# design.net
KiCad netlist of a schematic drawn in Altium Designer
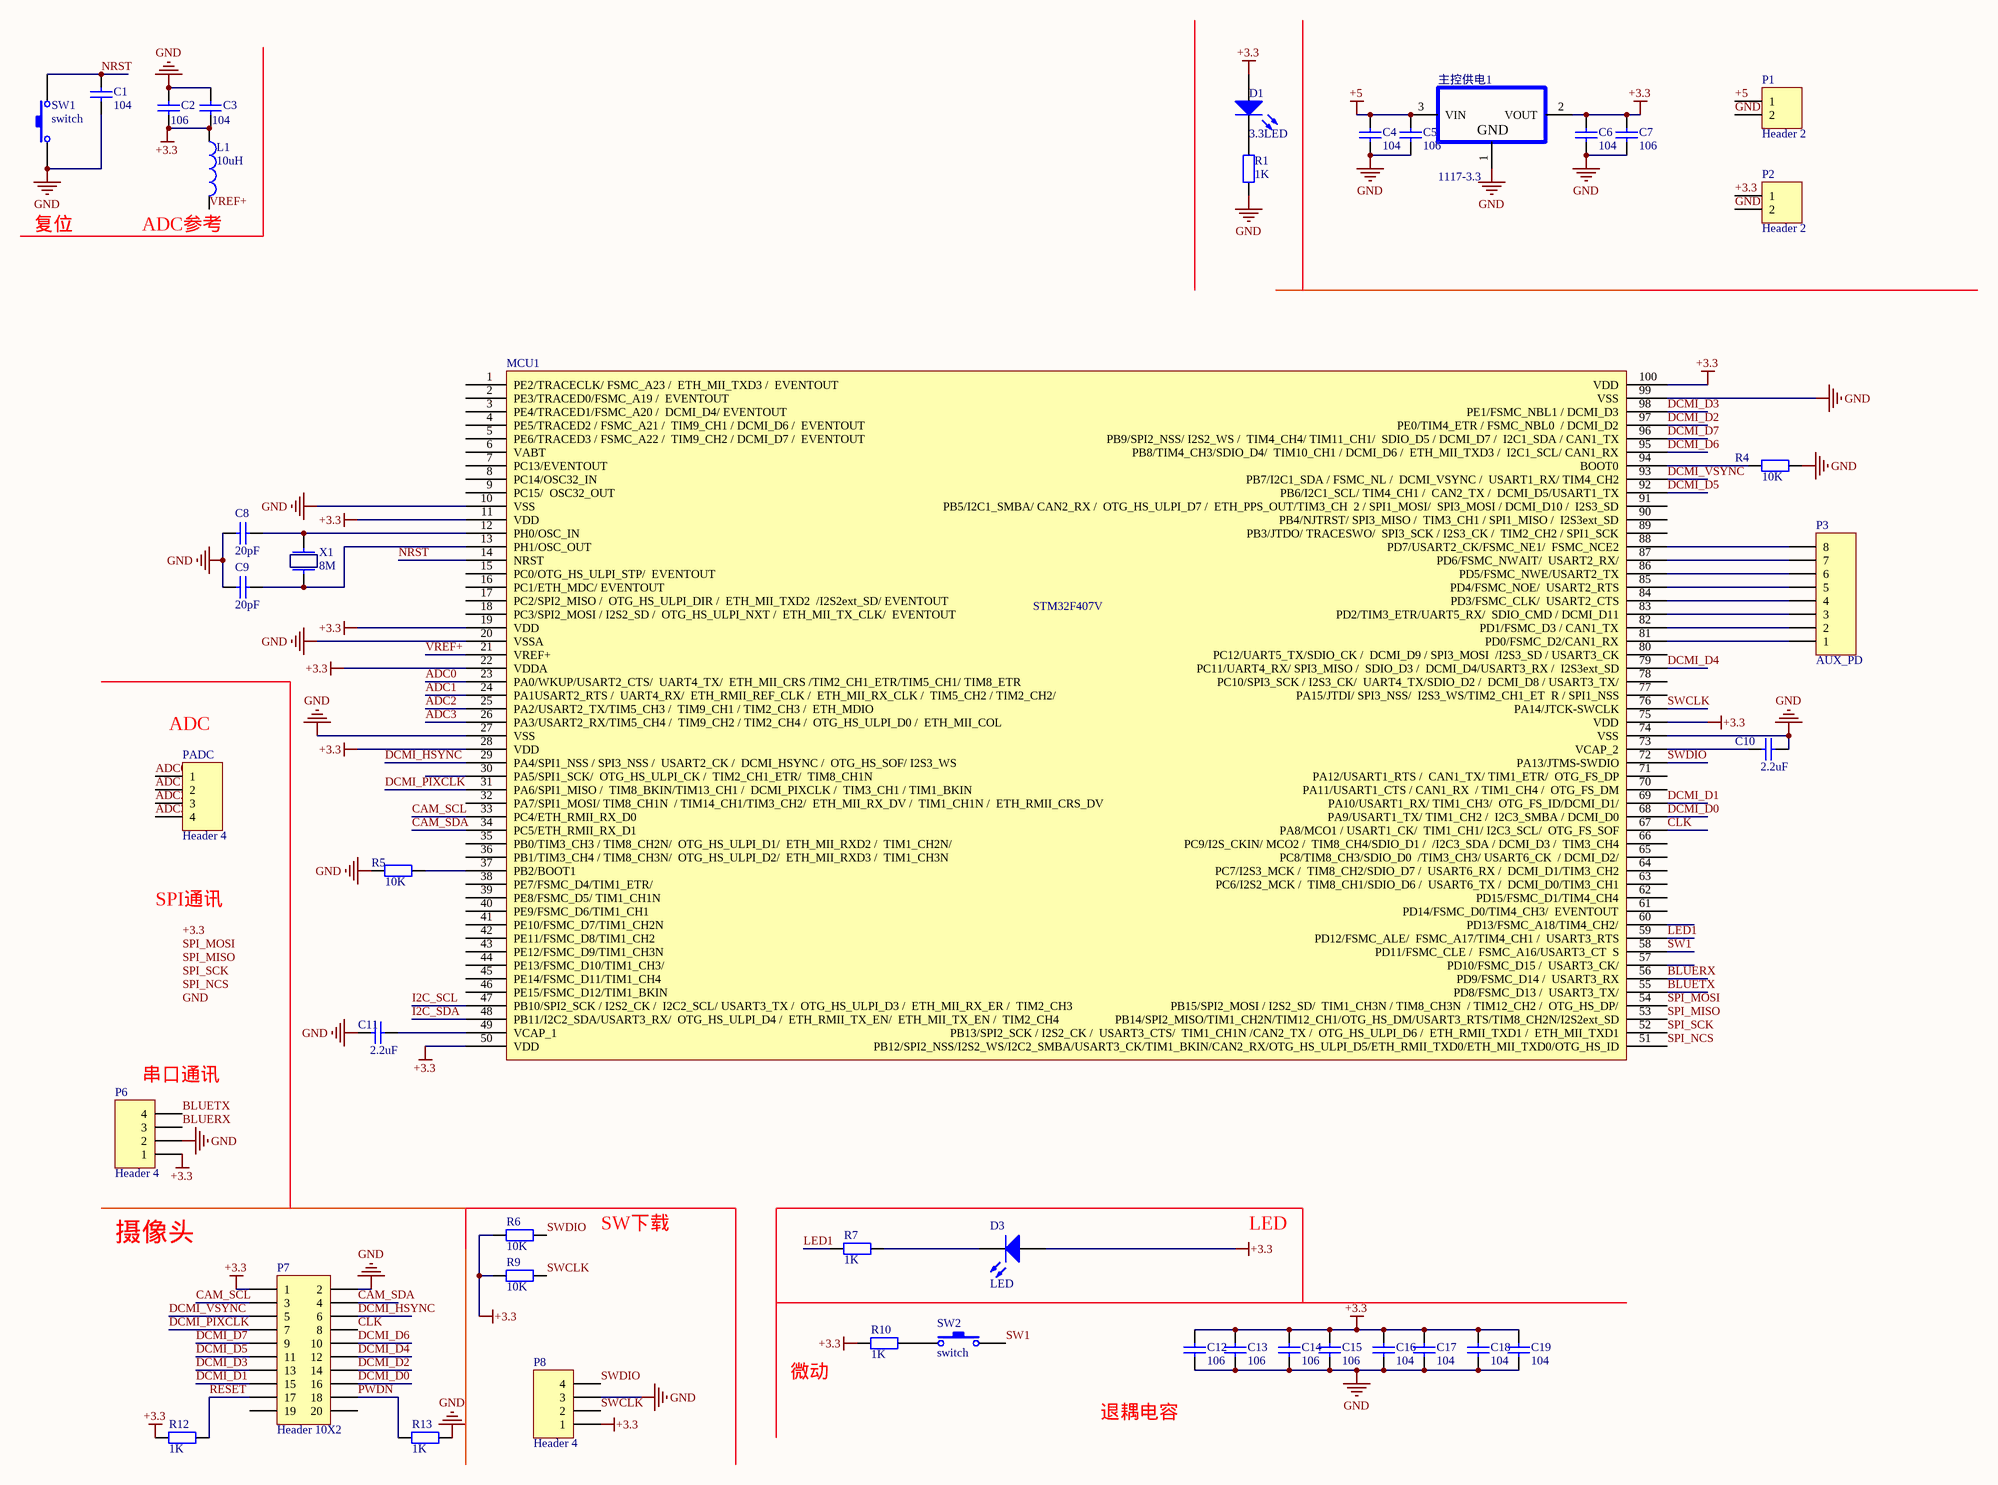
[diagram p0: 摄像头小王子.SchDoc]

(export (version "E")
  (design (tool "Eeschema 10.0.6"))
  (components
    (comp (ref "C1")
      (value "104")
      (footprint "6-0805_N")
      (libsource (lib "lucifer-PCBLIB_V2.0（这是老蒋的）") (part "cap"))
    )
    (comp (ref "C2")
      (value "106")
      (footprint "6-0805_N")
      (description "Capacitor")
      (fields (field (name "Comment") "Cap") (field (name "PUBLISHER") "Altium Limited"))
      (libsource (lib "Miscellaneous Devices") (part "Cap"))
    )
    (comp (ref "C3")
      (value "104")
      (footprint "6-0805_N")
      (description "Capacitor")
      (fields (field (name "Comment") "Cap") (field (name "PUBLISHER") "Altium Limited"))
      (libsource (lib "Miscellaneous Devices") (part "Cap"))
    )
    (comp (ref "C4")
      (value "104")
      (footprint "6-0805_N")
      (libsource (lib "lucifer-PCBLIB_V2.0（这是老蒋的）") (part "cap"))
    )
    (comp (ref "C5")
      (value "106")
      (footprint "6-0805_N")
      (libsource (lib "lucifer-PCBLIB_V2.0（这是老蒋的）") (part "cap"))
    )
    (comp (ref "C6")
      (value "104")
      (footprint "6-0805_N")
      (libsource (lib "lucifer-PCBLIB_V2.0（这是老蒋的）") (part "cap"))
    )
    (comp (ref "C7")
      (value "106")
      (footprint "6-0805_N")
      (libsource (lib "lucifer-PCBLIB_V2.0（这是老蒋的）") (part "cap"))
    )
    (comp (ref "C8")
      (value "20pF")
      (footprint "6-0805_N")
      (libsource (lib "lucifer-PCBLIB_V2.0（这是老蒋的）") (part "cap"))
    )
    (comp (ref "C9")
      (value "20pF")
      (footprint "6-0805_N")
      (libsource (lib "lucifer-PCBLIB_V2.0（这是老蒋的）") (part "cap"))
    )
    (comp (ref "C10")
      (value "2.2uF")
      (footprint "6-0805_N")
      (libsource (lib "lucifer-PCBLIB_V2.0（这是老蒋的）") (part "cap"))
    )
    (comp (ref "C11")
      (value "2.2uF")
      (footprint "6-0805_N")
      (libsource (lib "lucifer-PCBLIB_V2.0（这是老蒋的）") (part "cap"))
    )
    (comp (ref "C12")
      (value "106")
      (footprint "6-0805_N")
      (libsource (lib "lucifer-PCBLIB_V2.0（这是老蒋的）") (part "cap"))
    )
    (comp (ref "C13")
      (value "106")
      (footprint "6-0805_N")
      (libsource (lib "lucifer-PCBLIB_V2.0（这是老蒋的）") (part "cap"))
    )
    (comp (ref "C14")
      (value "106")
      (footprint "6-0805_N")
      (libsource (lib "lucifer-PCBLIB_V2.0（这是老蒋的）") (part "cap"))
    )
    (comp (ref "C15")
      (value "106")
      (footprint "6-0805_N")
      (libsource (lib "lucifer-PCBLIB_V2.0（这是老蒋的）") (part "cap"))
    )
    (comp (ref "C16")
      (value "104")
      (footprint "6-0805_N")
      (libsource (lib "lucifer-PCBLIB_V2.0（这是老蒋的）") (part "cap"))
    )
    (comp (ref "C17")
      (value "104")
      (footprint "6-0805_N")
      (libsource (lib "lucifer-PCBLIB_V2.0（这是老蒋的）") (part "cap"))
    )
    (comp (ref "C18")
      (value "104")
      (footprint "6-0805_N")
      (libsource (lib "lucifer-PCBLIB_V2.0（这是老蒋的）") (part "cap"))
    )
    (comp (ref "C19")
      (value "104")
      (footprint "6-0805_N")
      (libsource (lib "lucifer-PCBLIB_V2.0（这是老蒋的）") (part "cap"))
    )
    (comp (ref "D1")
      (value "3.3LED")
      (footprint "6-0805_N")
      (libsource (lib "lucifer-PCBLIB_V2.0（这是老蒋的）") (part "LED"))
    )
    (comp (ref "D3")
      (value "LED")
      (footprint "6-0805_N")
      (libsource (lib "lucifer-PCBLIB_V2.0（这是老蒋的）") (part "LED"))
    )
    (comp (ref "L1")
      (value "10uH")
      (footprint "6-0805_N")
      (description "Inductor")
      (fields (field (name "PUBLISHER") "Altium Limited"))
      (libsource (lib "Miscellaneous Devices") (part "Inductor"))
    )
    (comp (ref "MCU1") (value "STM32F407V") (footprint "LQFP100") (libsource (lib "我的库") (part "stm32f407")))
    (comp (ref "P1")
      (value "Header 2")
      (footprint "HDR1X2")
      (description "Header, 2-Pin")
      (fields (field (name "PUBLISHER") "Altium Limited"))
      (libsource (lib "Miscellaneous Connectors") (part "Header 2"))
    )
    (comp (ref "P2")
      (value "Header 2")
      (footprint "HDR1X2")
      (description "Header, 2-Pin")
      (fields (field (name "PUBLISHER") "Altium Limited"))
      (libsource (lib "Miscellaneous Connectors") (part "Header 2"))
    )
    (comp (ref "P3")
      (value "AUX_PD")
      (footprint "HDR1X8")
      (description "Header, 8-Pin")
      (fields (field (name "PUBLISHER") "Altium Limited"))
      (libsource (lib "Miscellaneous Connectors") (part "Header 8"))
    )
    (comp (ref "P6")
      (value "Header 4")
      (footprint "HDR1X4")
      (description "Header, 4-Pin")
      (fields (field (name "PUBLISHER") "Altium Limited"))
      (libsource (lib "Miscellaneous Connectors") (part "Header 4"))
    )
    (comp (ref "P7")
      (value "Header 10X2")
      (footprint "HDR2X10")
      (description "Header, 10-Pin, Dual row")
      (fields (field (name "PUBLISHER") "Altium Limited"))
      (libsource (lib "Miscellaneous Connectors") (part "Header 10X2"))
    )
    (comp (ref "P8")
      (value "Header 4")
      (footprint "HDR1X4")
      (description "Header, 4-Pin")
      (fields (field (name "PUBLISHER") "Altium Limited"))
      (libsource (lib "Miscellaneous Connectors") (part "Header 4"))
    )
    (comp (ref "PADC")
      (value "Header 4")
      (footprint "HDR1X4")
      (description "Header, 4-Pin")
      (fields (field (name "PUBLISHER") "Altium Limited"))
      (libsource (lib "") (part "Header 4_1"))
    )
    (comp (ref "R1")
      (value "1K")
      (footprint "6-0805_N")
      (description "small resistor")
      (libsource (lib "") (part "resistor_2"))
    )
    (comp (ref "R4")
      (value "10K")
      (footprint "6-0805_N")
      (description "small resistor")
      (libsource (lib "lucifer-PCBLIB_V2.0（这是老蒋的）") (part "resistor"))
    )
    (comp (ref "R5")
      (value "10K")
      (footprint "6-0805_N")
      (description "small resistor")
      (libsource (lib "") (part "resistor_1"))
    )
    (comp (ref "R6")
      (value "10K")
      (footprint "6-0805_N")
      (description "small resistor")
      (libsource (lib "lucifer-PCBLIB_V2.0（这是老蒋的）") (part "resistor"))
    )
    (comp (ref "R7")
      (value "1K")
      (footprint "6-0805_N")
      (description "small resistor")
      (libsource (lib "lucifer-PCBLIB_V2.0（这是老蒋的）") (part "resistor"))
    )
    (comp (ref "R9")
      (value "10K")
      (footprint "6-0805_N")
      (description "small resistor")
      (libsource (lib "") (part "resistor_1"))
    )
    (comp (ref "R10")
      (value "1K")
      (footprint "6-0805_N")
      (description "small resistor")
      (libsource (lib "lucifer-PCBLIB_V2.0（这是老蒋的）") (part "resistor"))
    )
    (comp (ref "R12")
      (value "1K")
      (footprint "6-0805_N")
      (description "small resistor")
      (libsource (lib "lucifer-PCBLIB_V2.0（这是老蒋的）") (part "resistor"))
    )
    (comp (ref "R13")
      (value "1K")
      (footprint "6-0805_N")
      (description "small resistor")
      (libsource (lib "lucifer-PCBLIB_V2.0（这是老蒋的）") (part "resistor"))
    )
    (comp (ref "SW1")
      (value "switch")
      (footprint "SW_PB2_A1")
      (libsource (lib "lucifer-PCBLIB_V2.0（这是老蒋的）") (part "switch-1"))
    )
    (comp (ref "SW2")
      (value "switch")
      (footprint "SW_PB2_A1")
      (libsource (lib "lucifer-PCBLIB_V2.0（这是老蒋的）") (part "switch-1"))
    )
    (comp (ref "X1")
      (value "8M")
      (footprint "HDR1X3")
      (fields (field (name "Comment") "xtal"))
      (libsource (lib "lucifer-PCBLIB_V2.0（这是老蒋的）") (part "xtal"))
    )
    (comp (ref "主控供电1")
      (value "1117-3.3")
      (footprint "SOT-223")
      (libsource (lib "lucifer-PCBLIB_V2.0（这是老蒋的）") (part "1117M3-3.3"))
    )
  )
  (nets
    (net (code "1") (name "+3.3") (class "Default")
      (node (ref "C12") (pin "2") (pinfunction "2_2") (pintype "passive"))
      (node (ref "C13") (pin "2") (pinfunction "2_2") (pintype "passive"))
      (node (ref "C14") (pin "2") (pinfunction "2_2") (pintype "passive"))
      (node (ref "C15") (pin "2") (pinfunction "2_2") (pintype "passive"))
      (node (ref "C16") (pin "2") (pinfunction "2_2") (pintype "passive"))
      (node (ref "C17") (pin "2") (pinfunction "2_2") (pintype "passive"))
      (node (ref "C18") (pin "2") (pinfunction "2_2") (pintype "passive"))
      (node (ref "C19") (pin "2") (pinfunction "2_2") (pintype "passive"))
      (node (ref "C2") (pin "1") (pinfunction "1_1") (pintype "passive"))
      (node (ref "C3") (pin "1") (pinfunction "1_1") (pintype "passive"))
      (node (ref "C6") (pin "2") (pinfunction "2_2") (pintype "passive"))
      (node (ref "C7") (pin "2") (pinfunction "2_2") (pintype "passive"))
      (node (ref "D1") (pin "1") (pinfunction "A_1") (pintype "passive"))
      (node (ref "D3") (pin "1") (pinfunction "A_1") (pintype "passive"))
      (node (ref "L1") (pin "1") (pinfunction "1_1") (pintype "passive"))
      (node (ref "MCU1") (pin "100") (pinfunction "VDD_100") (pintype "passive"))
      (node (ref "MCU1") (pin "11") (pinfunction "VDD_11") (pintype "passive"))
      (node (ref "MCU1") (pin "19") (pinfunction "VDD_19") (pintype "passive"))
      (node (ref "MCU1") (pin "22") (pinfunction "VDDA_22") (pintype "passive"))
      (node (ref "MCU1") (pin "28") (pinfunction "VDD_28") (pintype "passive"))
      (node (ref "MCU1") (pin "50") (pinfunction "VDD_50") (pintype "passive"))
      (node (ref "MCU1") (pin "75") (pinfunction "VDD_75") (pintype "passive"))
      (node (ref "P2") (pin "1") (pinfunction "1_1") (pintype "passive"))
      (node (ref "P6") (pin "1") (pinfunction "1_1") (pintype "passive"))
      (node (ref "P7") (pin "1") (pinfunction "1_1") (pintype "passive"))
      (node (ref "P8") (pin "1") (pinfunction "1_1") (pintype "passive"))
      (node (ref "R10") (pin "1") (pinfunction "1_1") (pintype "passive"))
      (node (ref "R12") (pin "1") (pinfunction "1_1") (pintype "passive"))
      (node (ref "R6") (pin "1") (pinfunction "1_1") (pintype "passive"))
      (node (ref "R9") (pin "2") (pinfunction "2_2") (pintype "passive"))
      (node (ref "主控供电1") (pin "2") (pinfunction "VOUT_2") (pintype "passive"))
    )
    (net (code "2") (name "+5") (class "Default")
      (node (ref "C4") (pin "2") (pinfunction "2_2") (pintype "passive"))
      (node (ref "C5") (pin "2") (pinfunction "2_2") (pintype "passive"))
      (node (ref "P1") (pin "1") (pinfunction "1_1") (pintype "passive"))
      (node (ref "主控供电1") (pin "3") (pinfunction "VIN_3") (pintype "passive"))
    )
    (net (code "3") (name "/ADC0") (class "Default")
      (node (ref "MCU1") (pin "23") (pinfunction "PA0/WKUP/USART2_CTS/__UART4_TX/__ETH_MII_CRS_/TIM2_CH1_ETR/TIM5_CH1/_TIM8_ETR_23") (pintype "passive"))
      (node (ref "PADC") (pin "1") (pinfunction "1_1") (pintype "passive"))
    )
    (net (code "4") (name "/ADC1") (class "Default")
      (node (ref "MCU1") (pin "24") (pinfunction "PA1USART2_RTS_/__UART4_RX/__ETH_RMII_REF_CLK_/__ETH_MII_RX_CLK_/__TIM5_CH2_/_TIM2_CH2/_24") (pintype "passive"))
      (node (ref "PADC") (pin "2") (pinfunction "2_2") (pintype "passive"))
    )
    (net (code "5") (name "/ADC2") (class "Default")
      (node (ref "MCU1") (pin "25") (pinfunction "PA2/USART2_TX/TIM5_CH3_/__TIM9_CH1_/_TIM2_CH3_/__ETH_MDIO_25") (pintype "passive"))
      (node (ref "PADC") (pin "3") (pinfunction "3_3") (pintype "passive"))
    )
    (net (code "6") (name "/ADC3") (class "Default")
      (node (ref "MCU1") (pin "26") (pinfunction "PA3/USART2_RX/TIM5_CH4_/__TIM9_CH2_/_TIM2_CH4_/__OTG_HS_ULPI_D0_/__ETH_MII_COL_26") (pintype "passive"))
      (node (ref "PADC") (pin "4") (pinfunction "4_4") (pintype "passive"))
    )
    (net (code "7") (name "/BLUERX") (class "Default")
      (node (ref "MCU1") (pin "56") (pinfunction "PD9/FSMC_D14_/__USART3_RX_56") (pintype "passive"))
      (node (ref "P6") (pin "3") (pinfunction "3_3") (pintype "passive"))
    )
    (net (code "8") (name "/BLUETX") (class "Default")
      (node (ref "MCU1") (pin "55") (pinfunction "PD8/FSMC_D13_/__USART3_TX/_55") (pintype "passive"))
      (node (ref "P6") (pin "4") (pinfunction "4_4") (pintype "passive"))
    )
    (net (code "9") (name "/CAM_SCL") (class "Default")
      (node (ref "MCU1") (pin "33") (pinfunction "PC4/ETH_RMII_RX_D0_33") (pintype "passive"))
      (node (ref "P7") (pin "3") (pinfunction "3_3") (pintype "passive"))
    )
    (net (code "10") (name "/CAM_SDA") (class "Default")
      (node (ref "MCU1") (pin "34") (pinfunction "PC5/ETH_RMII_RX_D1_34") (pintype "passive"))
      (node (ref "P7") (pin "4") (pinfunction "4_4") (pintype "passive"))
    )
    (net (code "11") (name "/CLK") (class "Default")
      (node (ref "MCU1") (pin "67") (pinfunction "PA8/MCO1_/_USART1_CK/__TIM1_CH1/_I2C3_SCL/__OTG_FS_SOF_67") (pintype "passive"))
      (node (ref "P7") (pin "8") (pinfunction "8_8") (pintype "passive"))
    )
    (net (code "12") (name "/DCMI_D0") (class "Default")
      (node (ref "MCU1") (pin "68") (pinfunction "PA9/USART1_TX/_TIM1_CH2_/__I2C3_SMBA_/_DCMI_D0_68") (pintype "passive"))
      (node (ref "P7") (pin "16") (pinfunction "16_16") (pintype "passive"))
    )
    (net (code "13") (name "/DCMI_D1") (class "Default")
      (node (ref "MCU1") (pin "69") (pinfunction "PA10/USART1_RX/_TIM1_CH3/__OTG_FS_ID/DCMI_D1/_69") (pintype "passive"))
      (node (ref "P7") (pin "15") (pinfunction "15_15") (pintype "passive"))
    )
    (net (code "14") (name "/DCMI_D2") (class "Default")
      (node (ref "MCU1") (pin "97") (pinfunction "PE0/TIM4_ETR_/_FSMC_NBL0__/_DCMI_D2_97") (pintype "passive"))
      (node (ref "P7") (pin "14") (pinfunction "14_14") (pintype "passive"))
    )
    (net (code "15") (name "/DCMI_D3") (class "Default")
      (node (ref "MCU1") (pin "98") (pinfunction "PE1/FSMC_NBL1_/_DCMI_D3_98") (pintype "passive"))
      (node (ref "P7") (pin "13") (pinfunction "13_13") (pintype "passive"))
    )
    (net (code "16") (name "/DCMI_D4") (class "Default")
      (node (ref "MCU1") (pin "79") (pinfunction "PC11/UART4_RX/_SPI3_MISO_/__SDIO_D3_/__DCMI_D4/USART3_RX_/__I2S3ext_SD_79") (pintype "passive"))
      (node (ref "P7") (pin "12") (pinfunction "12_12") (pintype "passive"))
    )
    (net (code "17") (name "/DCMI_D5") (class "Default")
      (node (ref "MCU1") (pin "92") (pinfunction "PB6/I2C1_SCL/_TIM4_CH1_/__CAN2_TX_/__DCMI_D5/USART1_TX_92") (pintype "passive"))
      (node (ref "P7") (pin "11") (pinfunction "11_11") (pintype "passive"))
    )
    (net (code "18") (name "/DCMI_D6") (class "Default")
      (node (ref "MCU1") (pin "95") (pinfunction "PB8/TIM4_CH3/SDIO_D4/__TIM10_CH1_/_DCMI_D6_/__ETH_MII_TXD3_/__I2C1_SCL/_CAN1_RX_95") (pintype "passive"))
      (node (ref "P7") (pin "10") (pinfunction "10_10") (pintype "passive"))
    )
    (net (code "19") (name "/DCMI_D7") (class "Default")
      (node (ref "MCU1") (pin "96") (pinfunction "PB9/SPI2_NSS/_I2S2_WS_/__TIM4_CH4/_TIM11_CH1/__SDIO_D5_/_DCMI_D7_/__I2C1_SDA_/_CAN1_TX_96") (pintype "passive"))
      (node (ref "P7") (pin "9") (pinfunction "9_9") (pintype "passive"))
    )
    (net (code "20") (name "/DCMI_HSYNC") (class "Default")
      (node (ref "MCU1") (pin "29") (pinfunction "PA4/SPI1_NSS_/_SPI3_NSS_/__USART2_CK_/__DCMI_HSYNC_/__OTG_HS_SOF/_I2S3_WS_29") (pintype "passive"))
      (node (ref "P7") (pin "6") (pinfunction "6_6") (pintype "passive"))
    )
    (net (code "21") (name "/DCMI_PIXCLK") (class "Default")
      (node (ref "MCU1") (pin "31") (pinfunction "PA6/SPI1_MISO_/__TIM8_BKIN/TIM13_CH1_/__DCMI_PIXCLK_/__TIM3_CH1_/_TIM1_BKIN_31") (pintype "passive"))
      (node (ref "P7") (pin "7") (pinfunction "7_7") (pintype "passive"))
    )
    (net (code "22") (name "/DCMI_VSYNC") (class "Default")
      (node (ref "MCU1") (pin "93") (pinfunction "PB7/I2C1_SDA_/_FSMC_NL_/__DCMI_VSYNC_/__USART1_RX/_TIM4_CH2_93") (pintype "passive"))
      (node (ref "P7") (pin "5") (pinfunction "5_5") (pintype "passive"))
    )
    (net (code "23") (name "/I2C_SCL") (class "Default")
      (node (ref "MCU1") (pin "47") (pinfunction "PB10/SPI2_SCK_/_I2S2_CK_/__I2C2_SCL/_USART3_TX_/__OTG_HS_ULPI_D3_/__ETH_MII_RX_ER_/__TIM2_CH3_47") (pintype "passive"))
    )
    (net (code "24") (name "/I2C_SDA") (class "Default")
      (node (ref "MCU1") (pin "48") (pinfunction "PB11/I2C2_SDA/USART3_RX/__OTG_HS_ULPI_D4_/__ETH_RMII_TX_EN/__ETH_MII_TX_EN_/__TIM2_CH4_48") (pintype "passive"))
    )
    (net (code "25") (name "/LED1") (class "Default")
      (node (ref "MCU1") (pin "59") (pinfunction "PD12/FSMC_ALE/__FSMC_A17/TIM4_CH1_/__USART3_RTS_59") (pintype "passive"))
      (node (ref "R7") (pin "1") (pinfunction "1_1") (pintype "passive"))
    )
    (net (code "26") (name "/NRST") (class "Default")
      (node (ref "C1") (pin "2") (pinfunction "2_2") (pintype "passive"))
      (node (ref "MCU1") (pin "14") (pinfunction "NRST_14") (pintype "passive"))
      (node (ref "SW1") (pin "2") (pinfunction "2_2") (pintype "passive"))
    )
    (net (code "27") (name "/PWDN") (class "Default")
      (node (ref "P7") (pin "18") (pinfunction "18_18") (pintype "passive"))
      (node (ref "R13") (pin "1") (pinfunction "1_1") (pintype "passive"))
    )
    (net (code "28") (name "/RESET") (class "Default")
      (node (ref "P7") (pin "17") (pinfunction "17_17") (pintype "passive"))
      (node (ref "R12") (pin "2") (pinfunction "2_2") (pintype "passive"))
    )
    (net (code "29") (name "/SPI_MISO") (class "Default")
      (node (ref "MCU1") (pin "53") (pinfunction "PB14/SPI2_MISO/TIM1_CH2N/TIM12_CH1/OTG_HS_DM/USART3_RTS/TIM8_CH2N/I2S2ext_SD_53") (pintype "passive"))
    )
    (net (code "30") (name "/SPI_MOSI") (class "Default")
      (node (ref "MCU1") (pin "54") (pinfunction "PB15/SPI2_MOSI_/_I2S2_SD/__TIM1_CH3N_/_TIM8_CH3N__/_TIM12_CH2_/__OTG_HS_DP/_54") (pintype "passive"))
    )
    (net (code "31") (name "/SPI_NCS") (class "Default")
      (node (ref "MCU1") (pin "51") (pinfunction "PB12/SPI2_NSS/I2S2_WS/I2C2_SMBA/USART3_CK/TIM1_BKIN/CAN2_RX/OTG_HS_ULPI_D5/ETH_RMII_TXD0/ETH_MII_TXD0/OTG_HS_ID_51") (pintype "passive"))
    )
    (net (code "32") (name "/SPI_SCK") (class "Default")
      (node (ref "MCU1") (pin "52") (pinfunction "PB13/SPI2_SCK_/_I2S2_CK_/__USART3_CTS/__TIM1_CH1N_/CAN2_TX_/__OTG_HS_ULPI_D6_/__ETH_RMII_TXD1_/__ETH_MII_TXD1_52") (pintype "passive"))
    )
    (net (code "33") (name "/SW1") (class "Default")
      (node (ref "MCU1") (pin "58") (pinfunction "PD11/FSMC_CLE_/__FSMC_A16/USART3_CT__S_58") (pintype "passive"))
      (node (ref "SW2") (pin "2") (pinfunction "2_2") (pintype "passive"))
    )
    (net (code "34") (name "/SWCLK") (class "Default")
      (node (ref "MCU1") (pin "76") (pinfunction "PA14/JTCK-SWCLK_76") (pintype "passive"))
      (node (ref "P8") (pin "2") (pinfunction "2_2") (pintype "passive"))
      (node (ref "R9") (pin "1") (pinfunction "1_1") (pintype "passive"))
    )
    (net (code "35") (name "/SWDIO") (class "Default")
      (node (ref "MCU1") (pin "72") (pinfunction "PA13/JTMS-SWDIO_72") (pintype "passive"))
      (node (ref "P8") (pin "4") (pinfunction "4_4") (pintype "passive"))
      (node (ref "R6") (pin "2") (pinfunction "2_2") (pintype "passive"))
    )
    (net (code "36") (name "/VREF+") (class "Default")
      (node (ref "L1") (pin "2") (pinfunction "2_2") (pintype "passive"))
      (node (ref "MCU1") (pin "21") (pinfunction "VREF+_21") (pintype "passive"))
    )
    (net (code "37") (name "GND") (class "Default")
      (node (ref "C1") (pin "1") (pinfunction "1_1") (pintype "passive"))
      (node (ref "C10") (pin "2") (pinfunction "2_2") (pintype "passive"))
      (node (ref "C11") (pin "1") (pinfunction "1_1") (pintype "passive"))
      (node (ref "C12") (pin "1") (pinfunction "1_1") (pintype "passive"))
      (node (ref "C13") (pin "1") (pinfunction "1_1") (pintype "passive"))
      (node (ref "C14") (pin "1") (pinfunction "1_1") (pintype "passive"))
      (node (ref "C15") (pin "1") (pinfunction "1_1") (pintype "passive"))
      (node (ref "C16") (pin "1") (pinfunction "1_1") (pintype "passive"))
      (node (ref "C17") (pin "1") (pinfunction "1_1") (pintype "passive"))
      (node (ref "C18") (pin "1") (pinfunction "1_1") (pintype "passive"))
      (node (ref "C19") (pin "1") (pinfunction "1_1") (pintype "passive"))
      (node (ref "C2") (pin "2") (pinfunction "2_2") (pintype "passive"))
      (node (ref "C3") (pin "2") (pinfunction "2_2") (pintype "passive"))
      (node (ref "C4") (pin "1") (pinfunction "1_1") (pintype "passive"))
      (node (ref "C5") (pin "1") (pinfunction "1_1") (pintype "passive"))
      (node (ref "C6") (pin "1") (pinfunction "1_1") (pintype "passive"))
      (node (ref "C7") (pin "1") (pinfunction "1_1") (pintype "passive"))
      (node (ref "C8") (pin "1") (pinfunction "1_1") (pintype "passive"))
      (node (ref "C9") (pin "1") (pinfunction "1_1") (pintype "passive"))
      (node (ref "MCU1") (pin "10") (pinfunction "VSS_10") (pintype "passive"))
      (node (ref "MCU1") (pin "20") (pinfunction "VSSA_20") (pintype "passive"))
      (node (ref "MCU1") (pin "27") (pinfunction "VSS_27") (pintype "passive"))
      (node (ref "MCU1") (pin "74") (pinfunction "VSS_74") (pintype "passive"))
      (node (ref "MCU1") (pin "99") (pinfunction "VSS_99") (pintype "passive"))
      (node (ref "P1") (pin "2") (pinfunction "2_2") (pintype "passive"))
      (node (ref "P2") (pin "2") (pinfunction "2_2") (pintype "passive"))
      (node (ref "P6") (pin "2") (pinfunction "2_2") (pintype "passive"))
      (node (ref "P7") (pin "2") (pinfunction "2_2") (pintype "passive"))
      (node (ref "P8") (pin "3") (pinfunction "3_3") (pintype "passive"))
      (node (ref "R1") (pin "1") (pinfunction "1_1") (pintype "passive"))
      (node (ref "R13") (pin "2") (pinfunction "2_2") (pintype "passive"))
      (node (ref "R4") (pin "2") (pinfunction "2_2") (pintype "passive"))
      (node (ref "R5") (pin "2") (pinfunction "2_2") (pintype "passive"))
      (node (ref "SW1") (pin "1") (pinfunction "1_1") (pintype "passive"))
      (node (ref "主控供电1") (pin "1") (pinfunction "GND_1") (pintype "passive"))
    )
    (net (code "38") (name "Net-(D1-K)") (class "Default")
      (node (ref "D1") (pin "2") (pinfunction "K_2") (pintype "passive"))
      (node (ref "R1") (pin "2") (pinfunction "2_2") (pintype "passive"))
    )
    (net (code "39") (name "Net-(D3-K)") (class "Default")
      (node (ref "D3") (pin "2") (pinfunction "K_2") (pintype "passive"))
      (node (ref "R7") (pin "2") (pinfunction "2_2") (pintype "passive"))
    )
    (net (code "40") (name "Net-(MCU1-BOOT0)") (class "Default")
      (node (ref "MCU1") (pin "94") (pinfunction "BOOT0_94") (pintype "passive"))
      (node (ref "R4") (pin "1") (pinfunction "1_1") (pintype "passive"))
    )
    (net (code "41") (name "Net-(MCU1-PB2{slash}BOOT1)") (class "Default")
      (node (ref "MCU1") (pin "37") (pinfunction "PB2/BOOT1_37") (pintype "passive"))
      (node (ref "R5") (pin "1") (pinfunction "1_1") (pintype "passive"))
    )
    (net (code "42") (name "Net-(MCU1-PD0{slash}FSMC_D2{slash}CAN1_RX)") (class "Default")
      (node (ref "MCU1") (pin "81") (pinfunction "PD0/FSMC_D2/CAN1_RX_81") (pintype "passive"))
      (node (ref "P3") (pin "1") (pinfunction "1_1") (pintype "passive"))
    )
    (net (code "43") (name "Net-(MCU1-PD1{slash}FSMC_D3_{slash}_CAN1_TX)") (class "Default")
      (node (ref "MCU1") (pin "82") (pinfunction "PD1/FSMC_D3_/_CAN1_TX_82") (pintype "passive"))
      (node (ref "P3") (pin "2") (pinfunction "2_2") (pintype "passive"))
    )
    (net (code "44") (name "Net-(MCU1-PD2{slash}TIM3_ETR{slash}UART5_RX{slash}__SDIO_CMD_{slash}_DCMI_D11)") (class "Default")
      (node (ref "MCU1") (pin "83") (pinfunction "PD2/TIM3_ETR/UART5_RX/__SDIO_CMD_/_DCMI_D11_83") (pintype "passive"))
      (node (ref "P3") (pin "3") (pinfunction "3_3") (pintype "passive"))
    )
    (net (code "45") (name "Net-(MCU1-PD3{slash}FSMC_CLK{slash}__USART2_CTS)") (class "Default")
      (node (ref "MCU1") (pin "84") (pinfunction "PD3/FSMC_CLK/__USART2_CTS_84") (pintype "passive"))
      (node (ref "P3") (pin "4") (pinfunction "4_4") (pintype "passive"))
    )
    (net (code "46") (name "Net-(MCU1-PD4{slash}FSMC_NOE{slash}__USART2_RTS)") (class "Default")
      (node (ref "MCU1") (pin "85") (pinfunction "PD4/FSMC_NOE/__USART2_RTS_85") (pintype "passive"))
      (node (ref "P3") (pin "5") (pinfunction "5_5") (pintype "passive"))
    )
    (net (code "47") (name "Net-(MCU1-PD5{slash}FSMC_NWE{slash}USART2_TX)") (class "Default")
      (node (ref "MCU1") (pin "86") (pinfunction "PD5/FSMC_NWE/USART2_TX_86") (pintype "passive"))
      (node (ref "P3") (pin "6") (pinfunction "6_6") (pintype "passive"))
    )
    (net (code "48") (name "Net-(MCU1-PD6{slash}FSMC_NWAIT{slash}__USART2_RX{slash})") (class "Default")
      (node (ref "MCU1") (pin "87") (pinfunction "PD6/FSMC_NWAIT/__USART2_RX/_87") (pintype "passive"))
      (node (ref "P3") (pin "7") (pinfunction "7_7") (pintype "passive"))
    )
    (net (code "49") (name "Net-(MCU1-PD7{slash}USART2_CK{slash}FSMC_NE1{slash}__FSMC_NCE2)") (class "Default")
      (node (ref "MCU1") (pin "88") (pinfunction "PD7/USART2_CK/FSMC_NE1/__FSMC_NCE2_88") (pintype "passive"))
      (node (ref "P3") (pin "8") (pinfunction "8_8") (pintype "passive"))
    )
    (net (code "50") (name "Net-(MCU1-PH0{slash}OSC_IN)") (class "Default")
      (node (ref "C8") (pin "2") (pinfunction "2_2") (pintype "passive"))
      (node (ref "MCU1") (pin "12") (pinfunction "PH0/OSC_IN_12") (pintype "passive"))
      (node (ref "X1") (pin "2") (pinfunction "2_2") (pintype "passive"))
    )
    (net (code "51") (name "Net-(MCU1-PH1{slash}OSC_OUT)") (class "Default")
      (node (ref "C9") (pin "2") (pinfunction "2_2") (pintype "passive"))
      (node (ref "MCU1") (pin "13") (pinfunction "PH1/OSC_OUT_13") (pintype "passive"))
      (node (ref "X1") (pin "1") (pinfunction "1_1") (pintype "passive"))
    )
    (net (code "52") (name "Net-(MCU1-VCAP_1)") (class "Default")
      (node (ref "C11") (pin "2") (pinfunction "2_2") (pintype "passive"))
      (node (ref "MCU1") (pin "49") (pinfunction "VCAP_1_49") (pintype "passive"))
    )
    (net (code "53") (name "Net-(MCU1-VCAP_2)") (class "Default")
      (node (ref "C10") (pin "1") (pinfunction "1_1") (pintype "passive"))
      (node (ref "MCU1") (pin "73") (pinfunction "VCAP_2_73") (pintype "passive"))
    )
    (net (code "54") (name "Net-(R10-Pad2)") (class "Default")
      (node (ref "R10") (pin "2") (pinfunction "2_2") (pintype "passive"))
      (node (ref "SW2") (pin "1") (pinfunction "1_1") (pintype "passive"))
    )
    (net (code "55") (name "unconnected-(MCU1-PA5{slash}SPI1_SCK{slash}__OTG_HS_ULPI_CK_{slash}__TIM2_CH1_ETR{slash}__TIM8_CH1N-Pad30)") (class "Default")
      (node (ref "MCU1") (pin "30") (pinfunction "PA5/SPI1_SCK/__OTG_HS_ULPI_CK_/__TIM2_CH1_ETR/__TIM8_CH1N_30") (pintype "passive"))
    )
    (net (code "56") (name "unconnected-(MCU1-PA7{slash}SPI1_MOSI{slash}_TIM8_CH1N__{slash}_TIM14_CH1{slash}TIM3_CH2{slash}__ETH_MII_RX_DV_{slash}__TIM1_CH1N_{slash}__ETH_RMII_CRS_DV-Pad32)") (class "Default")
      (node (ref "MCU1") (pin "32") (pinfunction "PA7/SPI1_MOSI/_TIM8_CH1N__/_TIM14_CH1/TIM3_CH2/__ETH_MII_RX_DV_/__TIM1_CH1N_/__ETH_RMII_CRS_DV_32") (pintype "passive"))
    )
    (net (code "57") (name "unconnected-(MCU1-PA11{slash}USART1_CTS_{slash}_CAN1_RX__{slash}_TIM1_CH4_{slash}__OTG_FS_DM-Pad70)") (class "Default")
      (node (ref "MCU1") (pin "70") (pinfunction "PA11/USART1_CTS_/_CAN1_RX__/_TIM1_CH4_/__OTG_FS_DM_70") (pintype "passive"))
    )
    (net (code "58") (name "unconnected-(MCU1-PA12{slash}USART1_RTS_{slash}__CAN1_TX{slash}_TIM1_ETR{slash}__OTG_FS_DP-Pad71)") (class "Default")
      (node (ref "MCU1") (pin "71") (pinfunction "PA12/USART1_RTS_/__CAN1_TX/_TIM1_ETR/__OTG_FS_DP_71") (pintype "passive"))
    )
    (net (code "59") (name "unconnected-(MCU1-PA15{slash}JTDI{slash}_SPI3_NSS{slash}__I2S3_WS{slash}TIM2_CH1_ET__R_{slash}_SPI1_NSS-Pad77)") (class "Default")
      (node (ref "MCU1") (pin "77") (pinfunction "PA15/JTDI/_SPI3_NSS/__I2S3_WS/TIM2_CH1_ET__R_/_SPI1_NSS_77") (pintype "passive"))
    )
    (net (code "60") (name "unconnected-(MCU1-PB0{slash}TIM3_CH3_{slash}_TIM8_CH2N{slash}__OTG_HS_ULPI_D1{slash}__ETH_MII_RXD2_{slash}__TIM1_CH2N{slash}-Pad35)") (class "Default")
      (node (ref "MCU1") (pin "35") (pinfunction "PB0/TIM3_CH3_/_TIM8_CH2N/__OTG_HS_ULPI_D1/__ETH_MII_RXD2_/__TIM1_CH2N/_35") (pintype "passive"))
    )
    (net (code "61") (name "unconnected-(MCU1-PB1{slash}TIM3_CH4_{slash}_TIM8_CH3N{slash}__OTG_HS_ULPI_D2{slash}__ETH_MII_RXD3_{slash}__TIM1_CH3N-Pad36)") (class "Default")
      (node (ref "MCU1") (pin "36") (pinfunction "PB1/TIM3_CH4_/_TIM8_CH3N/__OTG_HS_ULPI_D2/__ETH_MII_RXD3_/__TIM1_CH3N_36") (pintype "passive"))
    )
    (net (code "62") (name "unconnected-(MCU1-PB3{slash}JTDO{slash}_TRACESWO{slash}__SPI3_SCK_{slash}_I2S3_CK_{slash}__TIM2_CH2_{slash}_SPI1_SCK-Pad89)") (class "Default")
      (node (ref "MCU1") (pin "89") (pinfunction "PB3/JTDO/_TRACESWO/__SPI3_SCK_/_I2S3_CK_/__TIM2_CH2_/_SPI1_SCK_89") (pintype "passive"))
    )
    (net (code "63") (name "unconnected-(MCU1-PB4{slash}NJTRST{slash}_SPI3_MISO_{slash}__TIM3_CH1_{slash}_SPI1_MISO_{slash}__I2S3ext_SD-Pad90)") (class "Default")
      (node (ref "MCU1") (pin "90") (pinfunction "PB4/NJTRST/_SPI3_MISO_/__TIM3_CH1_/_SPI1_MISO_/__I2S3ext_SD_90") (pintype "passive"))
    )
    (net (code "64") (name "unconnected-(MCU1-PB5{slash}I2C1_SMBA{slash}_CAN2_RX_{slash}__OTG_HS_ULPI_D7_{slash}__ETH_PPS_OUT{slash}TIM3_CH__2_{slash}_SPI1_MOSI{slash}__SPI3_MOSI_{slash}_DCMI_D10_{slash}__I2S3_SD-Pad91)") (class "Default")
      (node (ref "MCU1") (pin "91") (pinfunction "PB5/I2C1_SMBA/_CAN2_RX_/__OTG_HS_ULPI_D7_/__ETH_PPS_OUT/TIM3_CH__2_/_SPI1_MOSI/__SPI3_MOSI_/_DCMI_D10_/__I2S3_SD_91") (pintype "passive"))
    )
    (net (code "65") (name "unconnected-(MCU1-PC0{slash}OTG_HS_ULPI_STP{slash}__EVENTOUT-Pad15)") (class "Default")
      (node (ref "MCU1") (pin "15") (pinfunction "PC0/OTG_HS_ULPI_STP/__EVENTOUT_15") (pintype "passive"))
    )
    (net (code "66") (name "unconnected-(MCU1-PC1{slash}ETH_MDC{slash}_EVENTOUT-Pad16)") (class "Default")
      (node (ref "MCU1") (pin "16") (pinfunction "PC1/ETH_MDC/_EVENTOUT_16") (pintype "passive"))
    )
    (net (code "67") (name "unconnected-(MCU1-PC2{slash}SPI2_MISO_{slash}__OTG_HS_ULPI_DIR_{slash}__ETH_MII_TXD2__{slash}I2S2ext_SD{slash}_EVENTOUT-Pad17)") (class "Default")
      (node (ref "MCU1") (pin "17") (pinfunction "PC2/SPI2_MISO_/__OTG_HS_ULPI_DIR_/__ETH_MII_TXD2__/I2S2ext_SD/_EVENTOUT_17") (pintype "passive"))
    )
    (net (code "68") (name "unconnected-(MCU1-PC3{slash}SPI2_MOSI_{slash}_I2S2_SD_{slash}__OTG_HS_ULPI_NXT_{slash}__ETH_MII_TX_CLK{slash}__EVENTOUT-Pad18)") (class "Default")
      (node (ref "MCU1") (pin "18") (pinfunction "PC3/SPI2_MOSI_/_I2S2_SD_/__OTG_HS_ULPI_NXT_/__ETH_MII_TX_CLK/__EVENTOUT_18") (pintype "passive"))
    )
    (net (code "69") (name "unconnected-(MCU1-PC6{slash}I2S2_MCK_{slash}__TIM8_CH1{slash}SDIO_D6_{slash}__USART6_TX_{slash}__DCMI_D0{slash}TIM3_CH1-Pad63)") (class "Default")
      (node (ref "MCU1") (pin "63") (pinfunction "PC6/I2S2_MCK_/__TIM8_CH1/SDIO_D6_/__USART6_TX_/__DCMI_D0/TIM3_CH1_63") (pintype "passive"))
    )
    (net (code "70") (name "unconnected-(MCU1-PC7{slash}I2S3_MCK_{slash}__TIM8_CH2{slash}SDIO_D7_{slash}__USART6_RX_{slash}__DCMI_D1{slash}TIM3_CH2-Pad64)") (class "Default")
      (node (ref "MCU1") (pin "64") (pinfunction "PC7/I2S3_MCK_/__TIM8_CH2/SDIO_D7_/__USART6_RX_/__DCMI_D1/TIM3_CH2_64") (pintype "passive"))
    )
    (net (code "71") (name "unconnected-(MCU1-PC8{slash}TIM8_CH3{slash}SDIO_D0__{slash}TIM3_CH3{slash}_USART6_CK__{slash}_DCMI_D2{slash}-Pad65)") (class "Default")
      (node (ref "MCU1") (pin "65") (pinfunction "PC8/TIM8_CH3/SDIO_D0__/TIM3_CH3/_USART6_CK__/_DCMI_D2/_65") (pintype "passive"))
    )
    (net (code "72") (name "unconnected-(MCU1-PC9{slash}I2S_CKIN{slash}_MCO2_{slash}__TIM8_CH4{slash}SDIO_D1_{slash}__{slash}I2C3_SDA_{slash}_DCMI_D3_{slash}__TIM3_CH4-Pad66)") (class "Default")
      (node (ref "MCU1") (pin "66") (pinfunction "PC9/I2S_CKIN/_MCO2_/__TIM8_CH4/SDIO_D1_/__/I2C3_SDA_/_DCMI_D3_/__TIM3_CH4_66") (pintype "passive"))
    )
    (net (code "73") (name "unconnected-(MCU1-PC10{slash}SPI3_SCK_{slash}_I2S3_CK{slash}__UART4_TX{slash}SDIO_D2_{slash}__DCMI_D8_{slash}_USART3_TX{slash}-Pad78)") (class "Default")
      (node (ref "MCU1") (pin "78") (pinfunction "PC10/SPI3_SCK_/_I2S3_CK/__UART4_TX/SDIO_D2_/__DCMI_D8_/_USART3_TX/_78") (pintype "passive"))
    )
    (net (code "74") (name "unconnected-(MCU1-PC12{slash}UART5_TX{slash}SDIO_CK_{slash}__DCMI_D9_{slash}_SPI3_MOSI__{slash}I2S3_SD_{slash}_USART3_CK-Pad80)") (class "Default")
      (node (ref "MCU1") (pin "80") (pinfunction "PC12/UART5_TX/SDIO_CK_/__DCMI_D9_/_SPI3_MOSI__/I2S3_SD_/_USART3_CK_80") (pintype "passive"))
    )
    (net (code "75") (name "unconnected-(MCU1-PC13{slash}EVENTOUT-Pad7)") (class "Default")
      (node (ref "MCU1") (pin "7") (pinfunction "PC13/EVENTOUT_7") (pintype "passive"))
    )
    (net (code "76") (name "unconnected-(MCU1-PC14{slash}OSC32_IN-Pad8)") (class "Default")
      (node (ref "MCU1") (pin "8") (pinfunction "PC14/OSC32_IN_8") (pintype "passive"))
    )
    (net (code "77") (name "unconnected-(MCU1-PC15{slash}__OSC32_OUT-Pad9)") (class "Default")
      (node (ref "MCU1") (pin "9") (pinfunction "PC15/__OSC32_OUT_9") (pintype "passive"))
    )
    (net (code "78") (name "unconnected-(MCU1-PD10{slash}FSMC_D15_{slash}__USART3_CK{slash}-Pad57)") (class "Default")
      (node (ref "MCU1") (pin "57") (pinfunction "PD10/FSMC_D15_/__USART3_CK/_57") (pintype "passive"))
    )
    (net (code "79") (name "unconnected-(MCU1-PD13{slash}FSMC_A18{slash}TIM4_CH2{slash}-Pad60)") (class "Default")
      (node (ref "MCU1") (pin "60") (pinfunction "PD13/FSMC_A18/TIM4_CH2/_60") (pintype "passive"))
    )
    (net (code "80") (name "unconnected-(MCU1-PD14{slash}FSMC_D0{slash}TIM4_CH3{slash}__EVENTOUT-Pad61)") (class "Default")
      (node (ref "MCU1") (pin "61") (pinfunction "PD14/FSMC_D0/TIM4_CH3/__EVENTOUT_61") (pintype "passive"))
    )
    (net (code "81") (name "unconnected-(MCU1-PD15{slash}FSMC_D1{slash}TIM4_CH4-Pad62)") (class "Default")
      (node (ref "MCU1") (pin "62") (pinfunction "PD15/FSMC_D1/TIM4_CH4_62") (pintype "passive"))
    )
    (net (code "82") (name "unconnected-(MCU1-PE2{slash}TRACECLK{slash}_FSMC_A23_{slash}__ETH_MII_TXD3_{slash}__EVENTOUT-Pad1)") (class "Default")
      (node (ref "MCU1") (pin "1") (pinfunction "PE2/TRACECLK/_FSMC_A23_/__ETH_MII_TXD3_/__EVENTOUT_1") (pintype "passive"))
    )
    (net (code "83") (name "unconnected-(MCU1-PE3{slash}TRACED0{slash}FSMC_A19_{slash}__EVENTOUT-Pad2)") (class "Default")
      (node (ref "MCU1") (pin "2") (pinfunction "PE3/TRACED0/FSMC_A19_/__EVENTOUT_2") (pintype "passive"))
    )
    (net (code "84") (name "unconnected-(MCU1-PE4{slash}TRACED1{slash}FSMC_A20_{slash}__DCMI_D4{slash}_EVENTOUT-Pad3)") (class "Default")
      (node (ref "MCU1") (pin "3") (pinfunction "PE4/TRACED1/FSMC_A20_/__DCMI_D4/_EVENTOUT_3") (pintype "passive"))
    )
    (net (code "85") (name "unconnected-(MCU1-PE5{slash}TRACED2_{slash}_FSMC_A21_{slash}__TIM9_CH1_{slash}_DCMI_D6_{slash}__EVENTOUT-Pad4)") (class "Default")
      (node (ref "MCU1") (pin "4") (pinfunction "PE5/TRACED2_/_FSMC_A21_/__TIM9_CH1_/_DCMI_D6_/__EVENTOUT_4") (pintype "passive"))
    )
    (net (code "86") (name "unconnected-(MCU1-PE6{slash}TRACED3_{slash}_FSMC_A22_{slash}__TIM9_CH2_{slash}_DCMI_D7_{slash}__EVENTOUT-Pad5)") (class "Default")
      (node (ref "MCU1") (pin "5") (pinfunction "PE6/TRACED3_/_FSMC_A22_/__TIM9_CH2_/_DCMI_D7_/__EVENTOUT_5") (pintype "passive"))
    )
    (net (code "87") (name "unconnected-(MCU1-PE7{slash}FSMC_D4{slash}TIM1_ETR{slash}-Pad38)") (class "Default")
      (node (ref "MCU1") (pin "38") (pinfunction "PE7/FSMC_D4/TIM1_ETR/_38") (pintype "passive"))
    )
    (net (code "88") (name "unconnected-(MCU1-PE8{slash}FSMC_D5{slash}_TIM1_CH1N-Pad39)") (class "Default")
      (node (ref "MCU1") (pin "39") (pinfunction "PE8/FSMC_D5/_TIM1_CH1N_39") (pintype "passive"))
    )
    (net (code "89") (name "unconnected-(MCU1-PE9{slash}FSMC_D6{slash}TIM1_CH1-Pad40)") (class "Default")
      (node (ref "MCU1") (pin "40") (pinfunction "PE9/FSMC_D6/TIM1_CH1_40") (pintype "passive"))
    )
    (net (code "90") (name "unconnected-(MCU1-PE10{slash}FSMC_D7{slash}TIM1_CH2N-Pad41)") (class "Default")
      (node (ref "MCU1") (pin "41") (pinfunction "PE10/FSMC_D7/TIM1_CH2N_41") (pintype "passive"))
    )
    (net (code "91") (name "unconnected-(MCU1-PE11{slash}FSMC_D8{slash}TIM1_CH2-Pad42)") (class "Default")
      (node (ref "MCU1") (pin "42") (pinfunction "PE11/FSMC_D8/TIM1_CH2_42") (pintype "passive"))
    )
    (net (code "92") (name "unconnected-(MCU1-PE12{slash}FSMC_D9{slash}TIM1_CH3N-Pad43)") (class "Default")
      (node (ref "MCU1") (pin "43") (pinfunction "PE12/FSMC_D9/TIM1_CH3N_43") (pintype "passive"))
    )
    (net (code "93") (name "unconnected-(MCU1-PE13{slash}FSMC_D10{slash}TIM1_CH3{slash}-Pad44)") (class "Default")
      (node (ref "MCU1") (pin "44") (pinfunction "PE13/FSMC_D10/TIM1_CH3/_44") (pintype "passive"))
    )
    (net (code "94") (name "unconnected-(MCU1-PE14{slash}FSMC_D11{slash}TIM1_CH4-Pad45)") (class "Default")
      (node (ref "MCU1") (pin "45") (pinfunction "PE14/FSMC_D11/TIM1_CH4_45") (pintype "passive"))
    )
    (net (code "95") (name "unconnected-(MCU1-PE15{slash}FSMC_D12{slash}TIM1_BKIN-Pad46)") (class "Default")
      (node (ref "MCU1") (pin "46") (pinfunction "PE15/FSMC_D12/TIM1_BKIN_46") (pintype "passive"))
    )
    (net (code "96") (name "unconnected-(MCU1-VABT-Pad6)") (class "Default")
      (node (ref "MCU1") (pin "6") (pinfunction "VABT_6") (pintype "passive"))
    )
    (net (code "97") (name "unconnected-(P7-Pad19)") (class "Default")
      (node (ref "P7") (pin "19") (pinfunction "19_19") (pintype "passive"))
    )
    (net (code "98") (name "unconnected-(P7-Pad20)") (class "Default")
      (node (ref "P7") (pin "20") (pinfunction "20_20") (pintype "passive"))
    )
  )
)
